# ADC_Buffers.net
KiCad netlist of a schematic drawn in Altium Designer
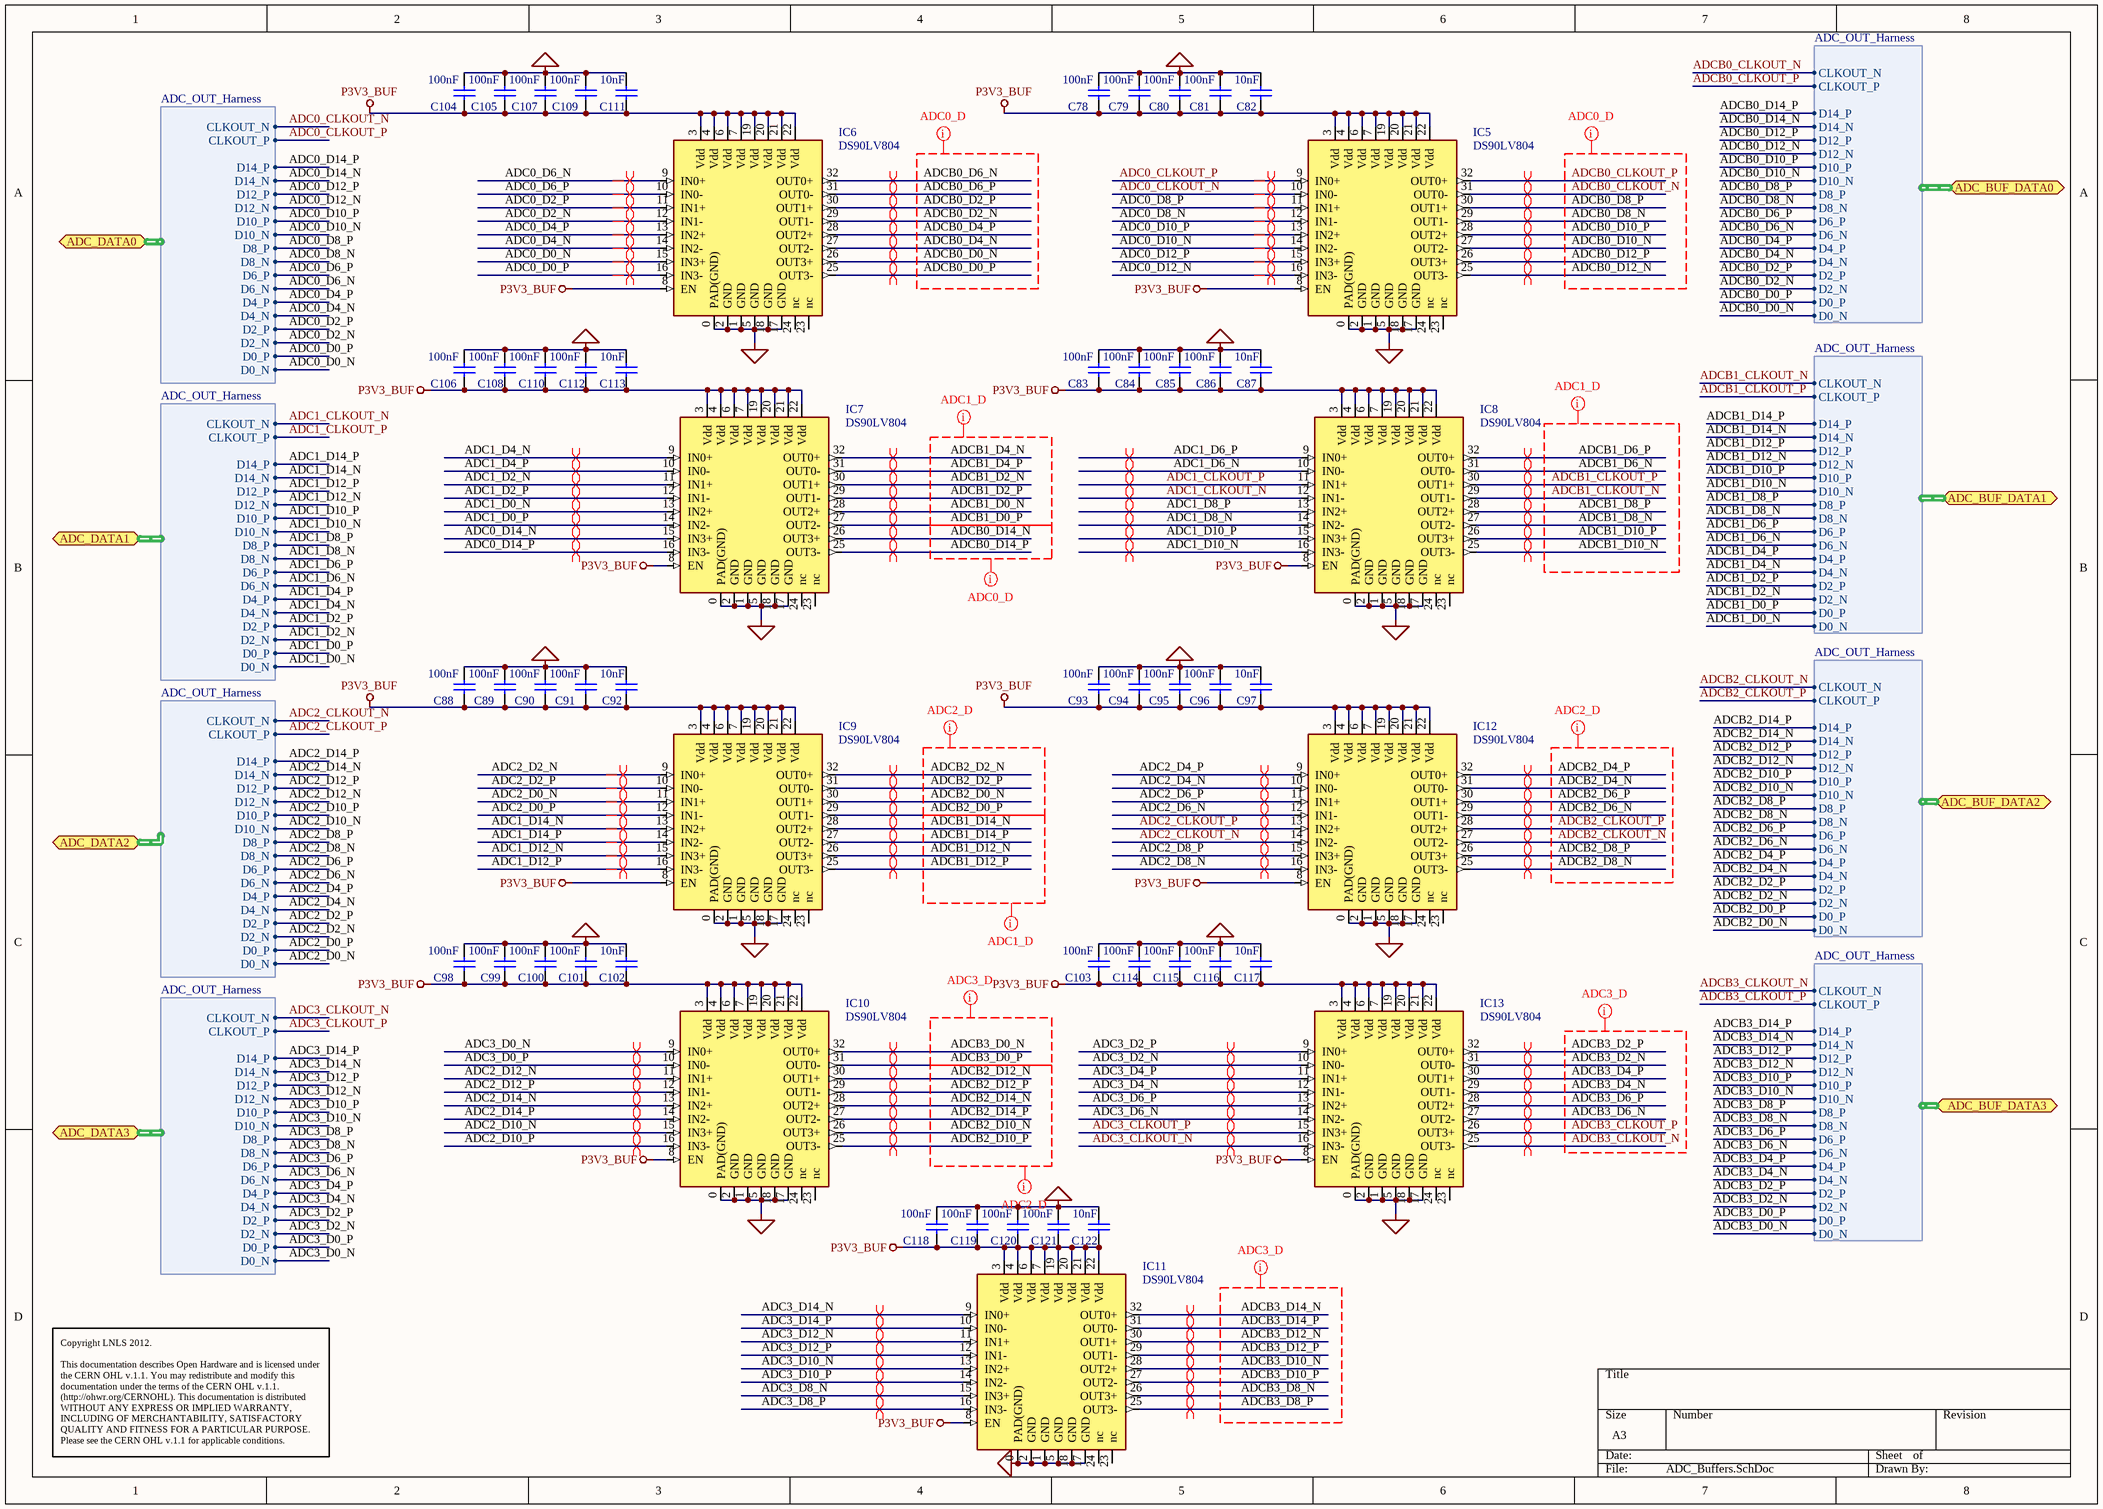
[diagram p0: ADC_Buffers.SchDoc]

(export (version "E")
  (design (tool "Eeschema 10.0.6"))
  (components
    (comp (ref "C78")
      (value "100nF")
      (footprint "CAPC0603X33N")
      (description "Non-polarised capacitor")
      (fields
        (field (name "PART NUMBER") "CC0201_100NF_6.3V_10%_X5R")
        (field (name "VOLTAGE") "6.3V")
        (field (name "AUTHOR") "CERN DEM JLC")
      )
      (libsource (lib "Capacitors") (part "Capacitor - non polarized"))
    )
    (comp (ref "C79")
      (value "100nF")
      (footprint "CAPC0603X33N")
      (description "Non-polarised capacitor")
      (fields
        (field (name "PART NUMBER") "CC0201_100NF_6.3V_10%_X5R")
        (field (name "VOLTAGE") "6.3V")
        (field (name "AUTHOR") "CERN DEM JLC")
      )
      (libsource (lib "Capacitors") (part "Capacitor - non polarized"))
    )
    (comp (ref "C80")
      (value "100nF")
      (footprint "CAPC0603X33N")
      (description "Non-polarised capacitor")
      (fields
        (field (name "PART NUMBER") "CC0201_100NF_6.3V_10%_X5R")
        (field (name "VOLTAGE") "6.3V")
        (field (name "AUTHOR") "CERN DEM JLC")
      )
      (libsource (lib "Capacitors") (part "Capacitor - non polarized"))
    )
    (comp (ref "C81")
      (value "100nF")
      (footprint "CAPC0603X33N")
      (description "Non-polarised capacitor")
      (fields
        (field (name "PART NUMBER") "CC0201_100NF_6.3V_10%_X5R")
        (field (name "VOLTAGE") "6.3V")
        (field (name "AUTHOR") "CERN DEM JLC")
      )
      (libsource (lib "Capacitors") (part "Capacitor - non polarized"))
    )
    (comp (ref "C82")
      (value "10nF")
      (footprint "CAPC0603X33N")
      (description "Non-polarised capacitor")
      (fields
        (field (name "PART NUMBER") "CC0201_10NF_10V_10%_X5R")
        (field (name "VOLTAGE") "10V")
        (field (name "AUTHOR") "CERN DEM JLC")
      )
      (libsource (lib "Capacitors") (part "Capacitor - non polarized"))
    )
    (comp (ref "C83")
      (value "100nF")
      (footprint "CAPC0603X33N")
      (description "Non-polarised capacitor")
      (fields
        (field (name "PART NUMBER") "CC0201_100NF_6.3V_10%_X5R")
        (field (name "VOLTAGE") "6.3V")
        (field (name "AUTHOR") "CERN DEM JLC")
      )
      (libsource (lib "Capacitors") (part "Capacitor - non polarized"))
    )
    (comp (ref "C84")
      (value "100nF")
      (footprint "CAPC0603X33N")
      (description "Non-polarised capacitor")
      (fields
        (field (name "PART NUMBER") "CC0201_100NF_6.3V_10%_X5R")
        (field (name "VOLTAGE") "6.3V")
        (field (name "AUTHOR") "CERN DEM JLC")
      )
      (libsource (lib "Capacitors") (part "Capacitor - non polarized"))
    )
    (comp (ref "C85")
      (value "100nF")
      (footprint "CAPC0603X33N")
      (description "Non-polarised capacitor")
      (fields
        (field (name "PART NUMBER") "CC0201_100NF_6.3V_10%_X5R")
        (field (name "VOLTAGE") "6.3V")
        (field (name "AUTHOR") "CERN DEM JLC")
      )
      (libsource (lib "Capacitors") (part "Capacitor - non polarized"))
    )
    (comp (ref "C86")
      (value "100nF")
      (footprint "CAPC0603X33N")
      (description "Non-polarised capacitor")
      (fields
        (field (name "PART NUMBER") "CC0201_100NF_6.3V_10%_X5R")
        (field (name "VOLTAGE") "6.3V")
        (field (name "AUTHOR") "CERN DEM JLC")
      )
      (libsource (lib "Capacitors") (part "Capacitor - non polarized"))
    )
    (comp (ref "C87")
      (value "10nF")
      (footprint "CAPC0603X33N")
      (description "Non-polarised capacitor")
      (fields
        (field (name "PART NUMBER") "CC0201_10NF_10V_10%_X5R")
        (field (name "VOLTAGE") "10V")
        (field (name "AUTHOR") "CERN DEM JLC")
      )
      (libsource (lib "Capacitors") (part "Capacitor - non polarized"))
    )
    (comp (ref "C88")
      (value "100nF")
      (footprint "CAPC0603X33N")
      (description "Non-polarised capacitor")
      (fields
        (field (name "PART NUMBER") "CC0201_100NF_6.3V_10%_X5R")
        (field (name "VOLTAGE") "6.3V")
        (field (name "AUTHOR") "CERN DEM JLC")
      )
      (libsource (lib "Capacitors") (part "Capacitor - non polarized"))
    )
    (comp (ref "C89")
      (value "100nF")
      (footprint "CAPC0603X33N")
      (description "Non-polarised capacitor")
      (fields
        (field (name "PART NUMBER") "CC0201_100NF_6.3V_10%_X5R")
        (field (name "VOLTAGE") "6.3V")
        (field (name "AUTHOR") "CERN DEM JLC")
      )
      (libsource (lib "Capacitors") (part "Capacitor - non polarized"))
    )
    (comp (ref "C90")
      (value "100nF")
      (footprint "CAPC0603X33N")
      (description "Non-polarised capacitor")
      (fields
        (field (name "PART NUMBER") "CC0201_100NF_6.3V_10%_X5R")
        (field (name "VOLTAGE") "6.3V")
        (field (name "AUTHOR") "CERN DEM JLC")
      )
      (libsource (lib "Capacitors") (part "Capacitor - non polarized"))
    )
    (comp (ref "C91")
      (value "100nF")
      (footprint "CAPC0603X33N")
      (description "Non-polarised capacitor")
      (fields
        (field (name "PART NUMBER") "CC0201_100NF_6.3V_10%_X5R")
        (field (name "VOLTAGE") "6.3V")
        (field (name "AUTHOR") "CERN DEM JLC")
      )
      (libsource (lib "Capacitors") (part "Capacitor - non polarized"))
    )
    (comp (ref "C92")
      (value "10nF")
      (footprint "CAPC0603X33N")
      (description "Non-polarised capacitor")
      (fields
        (field (name "PART NUMBER") "CC0201_10NF_10V_10%_X5R")
        (field (name "VOLTAGE") "10V")
        (field (name "AUTHOR") "CERN DEM JLC")
      )
      (libsource (lib "Capacitors") (part "Capacitor - non polarized"))
    )
    (comp (ref "C93")
      (value "100nF")
      (footprint "CAPC0603X33N")
      (description "Non-polarised capacitor")
      (fields
        (field (name "PART NUMBER") "CC0201_100NF_6.3V_10%_X5R")
        (field (name "VOLTAGE") "6.3V")
        (field (name "AUTHOR") "CERN DEM JLC")
      )
      (libsource (lib "Capacitors") (part "Capacitor - non polarized"))
    )
    (comp (ref "C94")
      (value "100nF")
      (footprint "CAPC0603X33N")
      (description "Non-polarised capacitor")
      (fields
        (field (name "PART NUMBER") "CC0201_100NF_6.3V_10%_X5R")
        (field (name "VOLTAGE") "6.3V")
        (field (name "AUTHOR") "CERN DEM JLC")
      )
      (libsource (lib "Capacitors") (part "Capacitor - non polarized"))
    )
    (comp (ref "C95")
      (value "100nF")
      (footprint "CAPC0603X33N")
      (description "Non-polarised capacitor")
      (fields
        (field (name "PART NUMBER") "CC0201_100NF_6.3V_10%_X5R")
        (field (name "VOLTAGE") "6.3V")
        (field (name "AUTHOR") "CERN DEM JLC")
      )
      (libsource (lib "Capacitors") (part "Capacitor - non polarized"))
    )
    (comp (ref "C96")
      (value "100nF")
      (footprint "CAPC0603X33N")
      (description "Non-polarised capacitor")
      (fields
        (field (name "PART NUMBER") "CC0201_100NF_6.3V_10%_X5R")
        (field (name "VOLTAGE") "6.3V")
        (field (name "AUTHOR") "CERN DEM JLC")
      )
      (libsource (lib "Capacitors") (part "Capacitor - non polarized"))
    )
    (comp (ref "C97")
      (value "10nF")
      (footprint "CAPC0603X33N")
      (description "Non-polarised capacitor")
      (fields
        (field (name "PART NUMBER") "CC0201_10NF_10V_10%_X5R")
        (field (name "VOLTAGE") "10V")
        (field (name "AUTHOR") "CERN DEM JLC")
      )
      (libsource (lib "Capacitors") (part "Capacitor - non polarized"))
    )
    (comp (ref "C98")
      (value "100nF")
      (footprint "CAPC0603X33N")
      (description "Non-polarised capacitor")
      (fields
        (field (name "PART NUMBER") "CC0201_100NF_6.3V_10%_X5R")
        (field (name "VOLTAGE") "6.3V")
        (field (name "AUTHOR") "CERN DEM JLC")
      )
      (libsource (lib "Capacitors") (part "Capacitor - non polarized"))
    )
    (comp (ref "C99")
      (value "100nF")
      (footprint "CAPC0603X33N")
      (description "Non-polarised capacitor")
      (fields
        (field (name "PART NUMBER") "CC0201_100NF_6.3V_10%_X5R")
        (field (name "VOLTAGE") "6.3V")
        (field (name "AUTHOR") "CERN DEM JLC")
      )
      (libsource (lib "Capacitors") (part "Capacitor - non polarized"))
    )
    (comp (ref "C100")
      (value "100nF")
      (footprint "CAPC0603X33N")
      (description "Non-polarised capacitor")
      (fields
        (field (name "PART NUMBER") "CC0201_100NF_6.3V_10%_X5R")
        (field (name "VOLTAGE") "6.3V")
        (field (name "AUTHOR") "CERN DEM JLC")
      )
      (libsource (lib "Capacitors") (part "Capacitor - non polarized"))
    )
    (comp (ref "C101")
      (value "100nF")
      (footprint "CAPC0603X33N")
      (description "Non-polarised capacitor")
      (fields
        (field (name "PART NUMBER") "CC0201_100NF_6.3V_10%_X5R")
        (field (name "VOLTAGE") "6.3V")
        (field (name "AUTHOR") "CERN DEM JLC")
      )
      (libsource (lib "Capacitors") (part "Capacitor - non polarized"))
    )
    (comp (ref "C102")
      (value "10nF")
      (footprint "CAPC0603X33N")
      (description "Non-polarised capacitor")
      (fields
        (field (name "PART NUMBER") "CC0201_10NF_10V_10%_X5R")
        (field (name "VOLTAGE") "10V")
        (field (name "AUTHOR") "CERN DEM JLC")
      )
      (libsource (lib "Capacitors") (part "Capacitor - non polarized"))
    )
    (comp (ref "C103")
      (value "100nF")
      (footprint "CAPC0603X33N")
      (description "Non-polarised capacitor")
      (fields
        (field (name "PART NUMBER") "CC0201_100NF_6.3V_10%_X5R")
        (field (name "VOLTAGE") "6.3V")
        (field (name "AUTHOR") "CERN DEM JLC")
      )
      (libsource (lib "Capacitors") (part "Capacitor - non polarized"))
    )
    (comp (ref "C104")
      (value "100nF")
      (footprint "CAPC0603X33N")
      (description "Non-polarised capacitor")
      (fields
        (field (name "PART NUMBER") "CC0201_100NF_6.3V_10%_X5R")
        (field (name "VOLTAGE") "6.3V")
        (field (name "AUTHOR") "CERN DEM JLC")
      )
      (libsource (lib "Capacitors") (part "Capacitor - non polarized"))
    )
    (comp (ref "C105")
      (value "100nF")
      (footprint "CAPC0603X33N")
      (description "Non-polarised capacitor")
      (fields
        (field (name "PART NUMBER") "CC0201_100NF_6.3V_10%_X5R")
        (field (name "VOLTAGE") "6.3V")
        (field (name "AUTHOR") "CERN DEM JLC")
      )
      (libsource (lib "Capacitors") (part "Capacitor - non polarized"))
    )
    (comp (ref "C106")
      (value "100nF")
      (footprint "CAPC0603X33N")
      (description "Non-polarised capacitor")
      (fields
        (field (name "PART NUMBER") "CC0201_100NF_6.3V_10%_X5R")
        (field (name "VOLTAGE") "6.3V")
        (field (name "AUTHOR") "CERN DEM JLC")
      )
      (libsource (lib "Capacitors") (part "Capacitor - non polarized"))
    )
    (comp (ref "C107")
      (value "100nF")
      (footprint "CAPC0603X33N")
      (description "Non-polarised capacitor")
      (fields
        (field (name "PART NUMBER") "CC0201_100NF_6.3V_10%_X5R")
        (field (name "VOLTAGE") "6.3V")
        (field (name "AUTHOR") "CERN DEM JLC")
      )
      (libsource (lib "Capacitors") (part "Capacitor - non polarized"))
    )
    (comp (ref "C108")
      (value "100nF")
      (footprint "CAPC0603X33N")
      (description "Non-polarised capacitor")
      (fields
        (field (name "PART NUMBER") "CC0201_100NF_6.3V_10%_X5R")
        (field (name "VOLTAGE") "6.3V")
        (field (name "AUTHOR") "CERN DEM JLC")
      )
      (libsource (lib "Capacitors") (part "Capacitor - non polarized"))
    )
    (comp (ref "C109")
      (value "100nF")
      (footprint "CAPC0603X33N")
      (description "Non-polarised capacitor")
      (fields
        (field (name "PART NUMBER") "CC0201_100NF_6.3V_10%_X5R")
        (field (name "VOLTAGE") "6.3V")
        (field (name "AUTHOR") "CERN DEM JLC")
      )
      (libsource (lib "Capacitors") (part "Capacitor - non polarized"))
    )
    (comp (ref "C110")
      (value "100nF")
      (footprint "CAPC0603X33N")
      (description "Non-polarised capacitor")
      (fields
        (field (name "PART NUMBER") "CC0201_100NF_6.3V_10%_X5R")
        (field (name "VOLTAGE") "6.3V")
        (field (name "AUTHOR") "CERN DEM JLC")
      )
      (libsource (lib "Capacitors") (part "Capacitor - non polarized"))
    )
    (comp (ref "C111")
      (value "10nF")
      (footprint "CAPC0603X33N")
      (description "Non-polarised capacitor")
      (fields
        (field (name "PART NUMBER") "CC0201_10NF_10V_10%_X5R")
        (field (name "VOLTAGE") "10V")
        (field (name "AUTHOR") "CERN DEM JLC")
      )
      (libsource (lib "Capacitors") (part "Capacitor - non polarized"))
    )
    (comp (ref "C112")
      (value "100nF")
      (footprint "CAPC0603X33N")
      (description "Non-polarised capacitor")
      (fields
        (field (name "PART NUMBER") "CC0201_100NF_6.3V_10%_X5R")
        (field (name "VOLTAGE") "6.3V")
        (field (name "AUTHOR") "CERN DEM JLC")
      )
      (libsource (lib "Capacitors") (part "Capacitor - non polarized"))
    )
    (comp (ref "C113")
      (value "10nF")
      (footprint "CAPC0603X33N")
      (description "Non-polarised capacitor")
      (fields
        (field (name "PART NUMBER") "CC0201_10NF_10V_10%_X5R")
        (field (name "VOLTAGE") "10V")
        (field (name "AUTHOR") "CERN DEM JLC")
      )
      (libsource (lib "Capacitors") (part "Capacitor - non polarized"))
    )
    (comp (ref "C114")
      (value "100nF")
      (footprint "CAPC0603X33N")
      (description "Non-polarised capacitor")
      (fields
        (field (name "PART NUMBER") "CC0201_100NF_6.3V_10%_X5R")
        (field (name "VOLTAGE") "6.3V")
        (field (name "AUTHOR") "CERN DEM JLC")
      )
      (libsource (lib "Capacitors") (part "Capacitor - non polarized"))
    )
    (comp (ref "C115")
      (value "100nF")
      (footprint "CAPC0603X33N")
      (description "Non-polarised capacitor")
      (fields
        (field (name "PART NUMBER") "CC0201_100NF_6.3V_10%_X5R")
        (field (name "VOLTAGE") "6.3V")
        (field (name "AUTHOR") "CERN DEM JLC")
      )
      (libsource (lib "Capacitors") (part "Capacitor - non polarized"))
    )
    (comp (ref "C116")
      (value "100nF")
      (footprint "CAPC0603X33N")
      (description "Non-polarised capacitor")
      (fields
        (field (name "PART NUMBER") "CC0201_100NF_6.3V_10%_X5R")
        (field (name "VOLTAGE") "6.3V")
        (field (name "AUTHOR") "CERN DEM JLC")
      )
      (libsource (lib "Capacitors") (part "Capacitor - non polarized"))
    )
    (comp (ref "C117")
      (value "10nF")
      (footprint "CAPC0603X33N")
      (description "Non-polarised capacitor")
      (fields
        (field (name "PART NUMBER") "CC0201_10NF_10V_10%_X5R")
        (field (name "VOLTAGE") "10V")
        (field (name "AUTHOR") "CERN DEM JLC")
      )
      (libsource (lib "Capacitors") (part "Capacitor - non polarized"))
    )
    (comp (ref "C118")
      (value "100nF")
      (footprint "CAPC0603X33N")
      (description "Non-polarised capacitor")
      (fields
        (field (name "PART NUMBER") "CC0201_100NF_6.3V_10%_X5R")
        (field (name "VOLTAGE") "6.3V")
        (field (name "AUTHOR") "CERN DEM JLC")
      )
      (libsource (lib "Capacitors") (part "Capacitor - non polarized"))
    )
    (comp (ref "C119")
      (value "100nF")
      (footprint "CAPC0603X33N")
      (description "Non-polarised capacitor")
      (fields
        (field (name "PART NUMBER") "CC0201_100NF_6.3V_10%_X5R")
        (field (name "VOLTAGE") "6.3V")
        (field (name "AUTHOR") "CERN DEM JLC")
      )
      (libsource (lib "Capacitors") (part "Capacitor - non polarized"))
    )
    (comp (ref "C120")
      (value "100nF")
      (footprint "CAPC0603X33N")
      (description "Non-polarised capacitor")
      (fields
        (field (name "PART NUMBER") "CC0201_100NF_6.3V_10%_X5R")
        (field (name "VOLTAGE") "6.3V")
        (field (name "AUTHOR") "CERN DEM JLC")
      )
      (libsource (lib "Capacitors") (part "Capacitor - non polarized"))
    )
    (comp (ref "C121")
      (value "100nF")
      (footprint "CAPC0603X33N")
      (description "Non-polarised capacitor")
      (fields
        (field (name "PART NUMBER") "CC0201_100NF_6.3V_10%_X5R")
        (field (name "VOLTAGE") "6.3V")
        (field (name "AUTHOR") "CERN DEM JLC")
      )
      (libsource (lib "Capacitors") (part "Capacitor - non polarized"))
    )
    (comp (ref "C122")
      (value "10nF")
      (footprint "CAPC0603X33N")
      (description "Non-polarised capacitor")
      (fields
        (field (name "PART NUMBER") "CC0201_10NF_10V_10%_X5R")
        (field (name "VOLTAGE") "10V")
        (field (name "AUTHOR") "CERN DEM JLC")
      )
      (libsource (lib "Capacitors") (part "Capacitor - non polarized"))
    )
    (comp (ref "IC5")
      (value "DS90LV804")
      (footprint "QFN50P500X500X80-33N-S320")
      (description "4-Channel 800 Mbps LVDS Buffer/Repeater")
      (fields
        (field (name "PART NUMBER") "DS90LV804TSQ")
        (field (name "MANUFACTURER") "TEXAS INSTRUMENTS")
        (field (name "AUTHOR") "LNLS DIG GBMB")
      )
      (libsource (lib "ICs And Semiconductors") (part "DS90LV804"))
    )
    (comp (ref "IC6")
      (value "DS90LV804")
      (footprint "QFN50P500X500X80-33N-S320")
      (description "4-Channel 800 Mbps LVDS Buffer/Repeater")
      (fields
        (field (name "PART NUMBER") "DS90LV804TSQ")
        (field (name "MANUFACTURER") "TEXAS INSTRUMENTS")
        (field (name "AUTHOR") "LNLS DIG GBMB")
      )
      (libsource (lib "ICs And Semiconductors") (part "DS90LV804"))
    )
    (comp (ref "IC7")
      (value "DS90LV804")
      (footprint "LFCSP32")
      (description "4-Channel 800 Mbps LVDS Buffer/Repeater")
      (fields
        (field (name "PART NUMBER") "DS90LV804TSQ")
        (field (name "MANUFACTURER") "TEXAS INSTRUMENTS")
        (field (name "AUTHOR") "LNLS DIG GBMB")
      )
      (libsource (lib "ICs And Semiconductors") (part "DS90LV804"))
    )
    (comp (ref "IC8")
      (value "DS90LV804")
      (footprint "LFCSP32")
      (description "4-Channel 800 Mbps LVDS Buffer/Repeater")
      (fields
        (field (name "PART NUMBER") "DS90LV804TSQ")
        (field (name "MANUFACTURER") "TEXAS INSTRUMENTS")
        (field (name "AUTHOR") "LNLS DIG GBMB")
      )
      (libsource (lib "ICs And Semiconductors") (part "DS90LV804"))
    )
    (comp (ref "IC9")
      (value "DS90LV804")
      (footprint "LFCSP32")
      (description "4-Channel 800 Mbps LVDS Buffer/Repeater")
      (fields
        (field (name "PART NUMBER") "DS90LV804TSQ")
        (field (name "MANUFACTURER") "TEXAS INSTRUMENTS")
        (field (name "AUTHOR") "LNLS DIG GBMB")
      )
      (libsource (lib "ICs And Semiconductors") (part "DS90LV804"))
    )
    (comp (ref "IC10")
      (value "DS90LV804")
      (footprint "LFCSP32")
      (description "4-Channel 800 Mbps LVDS Buffer/Repeater")
      (fields
        (field (name "PART NUMBER") "DS90LV804TSQ")
        (field (name "MANUFACTURER") "TEXAS INSTRUMENTS")
        (field (name "AUTHOR") "LNLS DIG GBMB")
      )
      (libsource (lib "ICs And Semiconductors") (part "DS90LV804"))
    )
    (comp (ref "IC11")
      (value "DS90LV804")
      (footprint "LFCSP32")
      (description "4-Channel 800 Mbps LVDS Buffer/Repeater")
      (fields
        (field (name "PART NUMBER") "DS90LV804TSQ")
        (field (name "MANUFACTURER") "TEXAS INSTRUMENTS")
        (field (name "AUTHOR") "LNLS DIG GBMB")
      )
      (libsource (lib "ICs And Semiconductors") (part "DS90LV804"))
    )
    (comp (ref "IC12")
      (value "DS90LV804")
      (footprint "LFCSP32")
      (description "4-Channel 800 Mbps LVDS Buffer/Repeater")
      (fields
        (field (name "PART NUMBER") "DS90LV804TSQ")
        (field (name "MANUFACTURER") "TEXAS INSTRUMENTS")
        (field (name "AUTHOR") "LNLS DIG GBMB")
      )
      (libsource (lib "ICs And Semiconductors") (part "DS90LV804"))
    )
    (comp (ref "IC13")
      (value "DS90LV804")
      (footprint "LFCSP32")
      (description "4-Channel 800 Mbps LVDS Buffer/Repeater")
      (fields
        (field (name "PART NUMBER") "DS90LV804TSQ")
        (field (name "MANUFACTURER") "TEXAS INSTRUMENTS")
        (field (name "AUTHOR") "LNLS DIG GBMB")
      )
      (libsource (lib "ICs And Semiconductors") (part "DS90LV804"))
    )
  )
  (nets
    (net (code "2") (name "/ADC0_CLKOUT_N") (class "Default")
      (node (ref "IC5") (pin "10") (pinfunction "IN0-_10") (pintype "input"))
    )
    (net (code "3") (name "/ADC0_CLKOUT_P") (class "Default")
      (node (ref "IC5") (pin "9") (pinfunction "IN0+_9") (pintype "input"))
    )
    (net (code "4") (name "/ADC0_D0_N") (class "Default")
      (node (ref "IC6") (pin "15") (pinfunction "IN3+_15") (pintype "input"))
    )
    (net (code "5") (name "/ADC0_D0_P") (class "Default")
      (node (ref "IC6") (pin "16") (pinfunction "IN3-_16") (pintype "input"))
    )
    (net (code "6") (name "/ADC0_D2_N") (class "Default")
      (node (ref "IC6") (pin "12") (pinfunction "IN1-_12") (pintype "input"))
    )
    (net (code "7") (name "/ADC0_D2_P") (class "Default")
      (node (ref "IC6") (pin "11") (pinfunction "IN1+_11") (pintype "input"))
    )
    (net (code "8") (name "/ADC0_D4_N") (class "Default")
      (node (ref "IC6") (pin "14") (pinfunction "IN2-_14") (pintype "input"))
    )
    (net (code "9") (name "/ADC0_D4_P") (class "Default")
      (node (ref "IC6") (pin "13") (pinfunction "IN2+_13") (pintype "input"))
    )
    (net (code "10") (name "/ADC0_D6_N") (class "Default")
      (node (ref "IC6") (pin "9") (pinfunction "IN0+_9") (pintype "input"))
    )
    (net (code "11") (name "/ADC0_D6_P") (class "Default")
      (node (ref "IC6") (pin "10") (pinfunction "IN0-_10") (pintype "input"))
    )
    (net (code "12") (name "/ADC0_D8_N") (class "Default")
      (node (ref "IC5") (pin "12") (pinfunction "IN1-_12") (pintype "input"))
    )
    (net (code "13") (name "/ADC0_D8_P") (class "Default")
      (node (ref "IC5") (pin "11") (pinfunction "IN1+_11") (pintype "input"))
    )
    (net (code "14") (name "/ADC0_D10_N") (class "Default")
      (node (ref "IC5") (pin "14") (pinfunction "IN2-_14") (pintype "input"))
    )
    (net (code "15") (name "/ADC0_D10_P") (class "Default")
      (node (ref "IC5") (pin "13") (pinfunction "IN2+_13") (pintype "input"))
    )
    (net (code "16") (name "/ADC0_D12_N") (class "Default")
      (node (ref "IC5") (pin "16") (pinfunction "IN3-_16") (pintype "input"))
    )
    (net (code "17") (name "/ADC0_D12_P") (class "Default")
      (node (ref "IC5") (pin "15") (pinfunction "IN3+_15") (pintype "input"))
    )
    (net (code "18") (name "/ADC0_D14_N") (class "Default")
      (node (ref "IC7") (pin "15") (pinfunction "IN3+_15") (pintype "input"))
    )
    (net (code "19") (name "/ADC0_D14_P") (class "Default")
      (node (ref "IC7") (pin "16") (pinfunction "IN3-_16") (pintype "input"))
    )
    (net (code "20") (name "/ADC1_CLKOUT_N") (class "Default")
      (node (ref "IC8") (pin "12") (pinfunction "IN1-_12") (pintype "input"))
    )
    (net (code "21") (name "/ADC1_CLKOUT_P") (class "Default")
      (node (ref "IC8") (pin "11") (pinfunction "IN1+_11") (pintype "input"))
    )
    (net (code "22") (name "/ADC1_D0_N") (class "Default")
      (node (ref "IC7") (pin "13") (pinfunction "IN2+_13") (pintype "input"))
    )
    (net (code "23") (name "/ADC1_D0_P") (class "Default")
      (node (ref "IC7") (pin "14") (pinfunction "IN2-_14") (pintype "input"))
    )
    (net (code "24") (name "/ADC1_D2_N") (class "Default")
      (node (ref "IC7") (pin "11") (pinfunction "IN1+_11") (pintype "input"))
    )
    (net (code "25") (name "/ADC1_D2_P") (class "Default")
      (node (ref "IC7") (pin "12") (pinfunction "IN1-_12") (pintype "input"))
    )
    (net (code "26") (name "/ADC1_D4_N") (class "Default")
      (node (ref "IC7") (pin "9") (pinfunction "IN0+_9") (pintype "input"))
    )
    (net (code "27") (name "/ADC1_D4_P") (class "Default")
      (node (ref "IC7") (pin "10") (pinfunction "IN0-_10") (pintype "input"))
    )
    (net (code "28") (name "/ADC1_D6_N") (class "Default")
      (node (ref "IC8") (pin "10") (pinfunction "IN0-_10") (pintype "input"))
    )
    (net (code "29") (name "/ADC1_D6_P") (class "Default")
      (node (ref "IC8") (pin "9") (pinfunction "IN0+_9") (pintype "input"))
    )
    (net (code "30") (name "/ADC1_D8_N") (class "Default")
      (node (ref "IC8") (pin "14") (pinfunction "IN2-_14") (pintype "input"))
    )
    (net (code "31") (name "/ADC1_D8_P") (class "Default")
      (node (ref "IC8") (pin "13") (pinfunction "IN2+_13") (pintype "input"))
    )
    (net (code "32") (name "/ADC1_D10_N") (class "Default")
      (node (ref "IC8") (pin "16") (pinfunction "IN3-_16") (pintype "input"))
    )
    (net (code "33") (name "/ADC1_D10_P") (class "Default")
      (node (ref "IC8") (pin "15") (pinfunction "IN3+_15") (pintype "input"))
    )
    (net (code "34") (name "/ADC1_D12_N") (class "Default")
      (node (ref "IC9") (pin "15") (pinfunction "IN3+_15") (pintype "input"))
    )
    (net (code "35") (name "/ADC1_D12_P") (class "Default")
      (node (ref "IC9") (pin "16") (pinfunction "IN3-_16") (pintype "input"))
    )
    (net (code "36") (name "/ADC1_D14_N") (class "Default")
      (node (ref "IC9") (pin "13") (pinfunction "IN2+_13") (pintype "input"))
    )
    (net (code "37") (name "/ADC1_D14_P") (class "Default")
      (node (ref "IC9") (pin "14") (pinfunction "IN2-_14") (pintype "input"))
    )
    (net (code "38") (name "/ADC2_CLKOUT_N") (class "Default")
      (node (ref "IC12") (pin "14") (pinfunction "IN2-_14") (pintype "input"))
    )
    (net (code "39") (name "/ADC2_CLKOUT_P") (class "Default")
      (node (ref "IC12") (pin "13") (pinfunction "IN2+_13") (pintype "input"))
    )
    (net (code "40") (name "/ADC2_D0_N") (class "Default")
      (node (ref "IC9") (pin "11") (pinfunction "IN1+_11") (pintype "input"))
    )
    (net (code "41") (name "/ADC2_D0_P") (class "Default")
      (node (ref "IC9") (pin "12") (pinfunction "IN1-_12") (pintype "input"))
    )
    (net (code "42") (name "/ADC2_D2_N") (class "Default")
      (node (ref "IC9") (pin "9") (pinfunction "IN0+_9") (pintype "input"))
    )
    (net (code "43") (name "/ADC2_D2_P") (class "Default")
      (node (ref "IC9") (pin "10") (pinfunction "IN0-_10") (pintype "input"))
    )
    (net (code "44") (name "/ADC2_D4_N") (class "Default")
      (node (ref "IC12") (pin "10") (pinfunction "IN0-_10") (pintype "input"))
    )
    (net (code "45") (name "/ADC2_D4_P") (class "Default")
      (node (ref "IC12") (pin "9") (pinfunction "IN0+_9") (pintype "input"))
    )
    (net (code "46") (name "/ADC2_D6_N") (class "Default")
      (node (ref "IC12") (pin "12") (pinfunction "IN1-_12") (pintype "input"))
    )
    (net (code "47") (name "/ADC2_D6_P") (class "Default")
      (node (ref "IC12") (pin "11") (pinfunction "IN1+_11") (pintype "input"))
    )
    (net (code "48") (name "/ADC2_D8_N") (class "Default")
      (node (ref "IC12") (pin "16") (pinfunction "IN3-_16") (pintype "input"))
    )
    (net (code "49") (name "/ADC2_D8_P") (class "Default")
      (node (ref "IC12") (pin "15") (pinfunction "IN3+_15") (pintype "input"))
    )
    (net (code "50") (name "/ADC2_D10_N") (class "Default")
      (node (ref "IC10") (pin "15") (pinfunction "IN3+_15") (pintype "input"))
    )
    (net (code "51") (name "/ADC2_D10_P") (class "Default")
      (node (ref "IC10") (pin "16") (pinfunction "IN3-_16") (pintype "input"))
    )
    (net (code "52") (name "/ADC2_D12_N") (class "Default")
      (node (ref "IC10") (pin "11") (pinfunction "IN1+_11") (pintype "input"))
    )
    (net (code "53") (name "/ADC2_D12_P") (class "Default")
      (node (ref "IC10") (pin "12") (pinfunction "IN1-_12") (pintype "input"))
    )
    (net (code "54") (name "/ADC2_D14_N") (class "Default")
      (node (ref "IC10") (pin "13") (pinfunction "IN2+_13") (pintype "input"))
    )
    (net (code "55") (name "/ADC2_D14_P") (class "Default")
      (node (ref "IC10") (pin "14") (pinfunction "IN2-_14") (pintype "input"))
    )
    (net (code "56") (name "/ADC3_CLKOUT_N") (class "Default")
      (node (ref "IC13") (pin "16") (pinfunction "IN3-_16") (pintype "input"))
    )
    (net (code "57") (name "/ADC3_CLKOUT_P") (class "Default")
      (node (ref "IC13") (pin "15") (pinfunction "IN3+_15") (pintype "input"))
    )
    (net (code "58") (name "/ADC3_D0_N") (class "Default")
      (node (ref "IC10") (pin "9") (pinfunction "IN0+_9") (pintype "input"))
    )
    (net (code "59") (name "/ADC3_D0_P") (class "Default")
      (node (ref "IC10") (pin "10") (pinfunction "IN0-_10") (pintype "input"))
    )
    (net (code "60") (name "/ADC3_D2_N") (class "Default")
      (node (ref "IC13") (pin "10") (pinfunction "IN0-_10") (pintype "input"))
    )
    (net (code "61") (name "/ADC3_D2_P") (class "Default")
      (node (ref "IC13") (pin "9") (pinfunction "IN0+_9") (pintype "input"))
    )
    (net (code "62") (name "/ADC3_D4_N") (class "Default")
      (node (ref "IC13") (pin "12") (pinfunction "IN1-_12") (pintype "input"))
    )
    (net (code "63") (name "/ADC3_D4_P") (class "Default")
      (node (ref "IC13") (pin "11") (pinfunction "IN1+_11") (pintype "input"))
    )
    (net (code "64") (name "/ADC3_D6_N") (class "Default")
      (node (ref "IC13") (pin "14") (pinfunction "IN2-_14") (pintype "input"))
    )
    (net (code "65") (name "/ADC3_D6_P") (class "Default")
      (node (ref "IC13") (pin "13") (pinfunction "IN2+_13") (pintype "input"))
    )
    (net (code "66") (name "/ADC3_D8_N") (class "Default")
      (node (ref "IC11") (pin "15") (pinfunction "IN3+_15") (pintype "input"))
    )
    (net (code "67") (name "/ADC3_D8_P") (class "Default")
      (node (ref "IC11") (pin "16") (pinfunction "IN3-_16") (pintype "input"))
    )
    (net (code "68") (name "/ADC3_D10_N") (class "Default")
      (node (ref "IC11") (pin "13") (pinfunction "IN2+_13") (pintype "input"))
    )
    (net (code "69") (name "/ADC3_D10_P") (class "Default")
      (node (ref "IC11") (pin "14") (pinfunction "IN2-_14") (pintype "input"))
    )
    (net (code "70") (name "/ADC3_D12_N") (class "Default")
      (node (ref "IC11") (pin "11") (pinfunction "IN1+_11") (pintype "input"))
    )
    (net (code "71") (name "/ADC3_D12_P") (class "Default")
      (node (ref "IC11") (pin "12") (pinfunction "IN1-_12") (pintype "input"))
    )
    (net (code "72") (name "/ADC3_D14_N") (class "Default")
      (node (ref "IC11") (pin "9") (pinfunction "IN0+_9") (pintype "input"))
    )
    (net (code "73") (name "/ADC3_D14_P") (class "Default")
      (node (ref "IC11") (pin "10") (pinfunction "IN0-_10") (pintype "input"))
    )
    (net (code "74") (name "/ADCB0_CLKOUT_N") (class "Default")
      (node (ref "IC5") (pin "31") (pinfunction "OUT0-_31") (pintype "output"))
    )
    (net (code "75") (name "/ADCB0_CLKOUT_P") (class "Default")
      (node (ref "IC5") (pin "32") (pinfunction "OUT0+_32") (pintype "output"))
    )
    (net (code "76") (name "/ADCB0_D0_N") (class "Default")
      (node (ref "IC6") (pin "26") (pinfunction "OUT3+_26") (pintype "output"))
    )
    (net (code "77") (name "/ADCB0_D0_P") (class "Default")
      (node (ref "IC6") (pin "25") (pinfunction "OUT3-_25") (pintype "output"))
    )
    (net (code "78") (name "/ADCB0_D2_N") (class "Default")
      (node (ref "IC6") (pin "29") (pinfunction "OUT1-_29") (pintype "output"))
    )
    (net (code "79") (name "/ADCB0_D2_P") (class "Default")
      (node (ref "IC6") (pin "30") (pinfunction "OUT1+_30") (pintype "output"))
    )
    (net (code "80") (name "/ADCB0_D4_N") (class "Default")
      (node (ref "IC6") (pin "27") (pinfunction "OUT2-_27") (pintype "output"))
    )
    (net (code "81") (name "/ADCB0_D4_P") (class "Default")
      (node (ref "IC6") (pin "28") (pinfunction "OUT2+_28") (pintype "output"))
    )
    (net (code "82") (name "/ADCB0_D6_N") (class "Default")
      (node (ref "IC6") (pin "32") (pinfunction "OUT0+_32") (pintype "output"))
    )
    (net (code "83") (name "/ADCB0_D6_P") (class "Default")
      (node (ref "IC6") (pin "31") (pinfunction "OUT0-_31") (pintype "output"))
    )
    (net (code "84") (name "/ADCB0_D8_N") (class "Default")
      (node (ref "IC5") (pin "29") (pinfunction "OUT1-_29") (pintype "output"))
    )
    (net (code "85") (name "/ADCB0_D8_P") (class "Default")
      (node (ref "IC5") (pin "30") (pinfunction "OUT1+_30") (pintype "output"))
    )
    (net (code "86") (name "/ADCB0_D10_N") (class "Default")
      (node (ref "IC5") (pin "27") (pinfunction "OUT2-_27") (pintype "output"))
    )
    (net (code "87") (name "/ADCB0_D10_P") (class "Default")
      (node (ref "IC5") (pin "28") (pinfunction "OUT2+_28") (pintype "output"))
    )
    (net (code "88") (name "/ADCB0_D12_N") (class "Default")
      (node (ref "IC5") (pin "25") (pinfunction "OUT3-_25") (pintype "output"))
    )
    (net (code "89") (name "/ADCB0_D12_P") (class "Default")
      (node (ref "IC5") (pin "26") (pinfunction "OUT3+_26") (pintype "output"))
    )
    (net (code "90") (name "/ADCB0_D14_N") (class "Default")
      (node (ref "IC7") (pin "26") (pinfunction "OUT3+_26") (pintype "output"))
    )
    (net (code "91") (name "/ADCB0_D14_P") (class "Default")
      (node (ref "IC7") (pin "25") (pinfunction "OUT3-_25") (pintype "output"))
    )
    (net (code "92") (name "/ADCB1_CLKOUT_N") (class "Default")
      (node (ref "IC8") (pin "29") (pinfunction "OUT1-_29") (pintype "output"))
    )
    (net (code "93") (name "/ADCB1_CLKOUT_P") (class "Default")
      (node (ref "IC8") (pin "30") (pinfunction "OUT1+_30") (pintype "output"))
    )
    (net (code "94") (name "/ADCB1_D0_N") (class "Default")
      (node (ref "IC7") (pin "28") (pinfunction "OUT2+_28") (pintype "output"))
    )
    (net (code "95") (name "/ADCB1_D0_P") (class "Default")
      (node (ref "IC7") (pin "27") (pinfunction "OUT2-_27") (pintype "output"))
    )
    (net (code "96") (name "/ADCB1_D2_N") (class "Default")
      (node (ref "IC7") (pin "30") (pinfunction "OUT1+_30") (pintype "output"))
    )
    (net (code "97") (name "/ADCB1_D2_P") (class "Default")
      (node (ref "IC7") (pin "29") (pinfunction "OUT1-_29") (pintype "output"))
    )
    (net (code "98") (name "/ADCB1_D4_N") (class "Default")
      (node (ref "IC7") (pin "32") (pinfunction "OUT0+_32") (pintype "output"))
    )
    (net (code "99") (name "/ADCB1_D4_P") (class "Default")
      (node (ref "IC7") (pin "31") (pinfunction "OUT0-_31") (pintype "output"))
    )
    (net (code "100") (name "/ADCB1_D6_N") (class "Default")
      (node (ref "IC8") (pin "31") (pinfunction "OUT0-_31") (pintype "output"))
    )
    (net (code "101") (name "/ADCB1_D6_P") (class "Default")
      (node (ref "IC8") (pin "32") (pinfunction "OUT0+_32") (pintype "output"))
    )
    (net (code "102") (name "/ADCB1_D8_N") (class "Default")
      (node (ref "IC8") (pin "27") (pinfunction "OUT2-_27") (pintype "output"))
    )
    (net (code "103") (name "/ADCB1_D8_P") (class "Default")
      (node (ref "IC8") (pin "28") (pinfunction "OUT2+_28") (pintype "output"))
    )
    (net (code "104") (name "/ADCB1_D10_N") (class "Default")
      (node (ref "IC8") (pin "25") (pinfunction "OUT3-_25") (pintype "output"))
    )
    (net (code "105") (name "/ADCB1_D10_P") (class "Default")
      (node (ref "IC8") (pin "26") (pinfunction "OUT3+_26") (pintype "output"))
    )
    (net (code "106") (name "/ADCB1_D12_N") (class "Default")
      (node (ref "IC9") (pin "26") (pinfunction "OUT3+_26") (pintype "output"))
    )
    (net (code "107") (name "/ADCB1_D12_P") (class "Default")
      (node (ref "IC9") (pin "25") (pinfunction "OUT3-_25") (pintype "output"))
    )
    (net (code "108") (name "/ADCB1_D14_N") (class "Default")
      (node (ref "IC9") (pin "28") (pinfunction "OUT2+_28") (pintype "output"))
    )
    (net (code "109") (name "/ADCB1_D14_P") (class "Default")
      (node (ref "IC9") (pin "27") (pinfunction "OUT2-_27") (pintype "output"))
    )
    (net (code "110") (name "/ADCB2_CLKOUT_N") (class "Default")
      (node (ref "IC12") (pin "27") (pinfunction "OUT2-_27") (pintype "output"))
    )
    (net (code "111") (name "/ADCB2_CLKOUT_P") (class "Default")
      (node (ref "IC12") (pin "28") (pinfunction "OUT2+_28") (pintype "output"))
    )
    (net (code "112") (name "/ADCB2_D0_N") (class "Default")
      (node (ref "IC9") (pin "30") (pinfunction "OUT1+_30") (pintype "output"))
    )
    (net (code "113") (name "/ADCB2_D0_P") (class "Default")
      (node (ref "IC9") (pin "29") (pinfunction "OUT1-_29") (pintype "output"))
    )
    (net (code "114") (name "/ADCB2_D2_N") (class "Default")
      (node (ref "IC9") (pin "32") (pinfunction "OUT0+_32") (pintype "output"))
    )
    (net (code "115") (name "/ADCB2_D2_P") (class "Default")
      (node (ref "IC9") (pin "31") (pinfunction "OUT0-_31") (pintype "output"))
    )
    (net (code "116") (name "/ADCB2_D4_N") (class "Default")
      (node (ref "IC12") (pin "31") (pinfunction "OUT0-_31") (pintype "output"))
    )
    (net (code "117") (name "/ADCB2_D4_P") (class "Default")
      (node (ref "IC12") (pin "32") (pinfunction "OUT0+_32") (pintype "output"))
    )
    (net (code "118") (name "/ADCB2_D6_N") (class "Default")
      (node (ref "IC12") (pin "29") (pinfunction "OUT1-_29") (pintype "output"))
    )
    (net (code "119") (name "/ADCB2_D6_P") (class "Default")
      (node (ref "IC12") (pin "30") (pinfunction "OUT1+_30") (pintype "output"))
    )
    (net (code "120") (name "/ADCB2_D8_N") (class "Default")
      (node (ref "IC12") (pin "25") (pinfunction "OUT3-_25") (pintype "output"))
    )
    (net (code "121") (name "/ADCB2_D8_P") (class "Default")
      (node (ref "IC12") (pin "26") (pinfunction "OUT3+_26") (pintype "output"))
    )
    (net (code "122") (name "/ADCB2_D10_N") (class "Default")
      (node (ref "IC10") (pin "26") (pinfunction "OUT3+_26") (pintype "output"))
    )
    (net (code "123") (name "/ADCB2_D10_P") (class "Default")
      (node (ref "IC10") (pin "25") (pinfunction "OUT3-_25") (pintype "output"))
    )
    (net (code "124") (name "/ADCB2_D12_N") (class "Default")
      (node (ref "IC10") (pin "30") (pinfunction "OUT1+_30") (pintype "output"))
    )
    (net (code "125") (name "/ADCB2_D12_P") (class "Default")
      (node (ref "IC10") (pin "29") (pinfunction "OUT1-_29") (pintype "output"))
    )
    (net (code "126") (name "/ADCB2_D14_N") (class "Default")
      (node (ref "IC10") (pin "28") (pinfunction "OUT2+_28") (pintype "output"))
    )
    (net (code "127") (name "/ADCB2_D14_P") (class "Default")
      (node (ref "IC10") (pin "27") (pinfunction "OUT2-_27") (pintype "output"))
    )
    (net (code "128") (name "/ADCB3_CLKOUT_N") (class "Default")
      (node (ref "IC13") (pin "25") (pinfunction "OUT3-_25") (pintype "output"))
    )
    (net (code "129") (name "/ADCB3_CLKOUT_P") (class "Default")
      (node (ref "IC13") (pin "26") (pinfunction "OUT3+_26") (pintype "output"))
    )
    (net (code "130") (name "/ADCB3_D0_N") (class "Default")
      (node (ref "IC10") (pin "32") (pinfunction "OUT0+_32") (pintype "output"))
    )
    (net (code "131") (name "/ADCB3_D0_P") (class "Default")
      (node (ref "IC10") (pin "31") (pinfunction "OUT0-_31") (pintype "output"))
    )
    (net (code "132") (name "/ADCB3_D2_N") (class "Default")
      (node (ref "IC13") (pin "31") (pinfunction "OUT0-_31") (pintype "output"))
    )
    (net (code "133") (name "/ADCB3_D2_P") (class "Default")
      (node (ref "IC13") (pin "32") (pinfunction "OUT0+_32") (pintype "output"))
    )
    (net (code "134") (name "/ADCB3_D4_N") (class "Default")
      (node (ref "IC13") (pin "29") (pinfunction "OUT1-_29") (pintype "output"))
    )
    (net (code "135") (name "/ADCB3_D4_P") (class "Default")
      (node (ref "IC13") (pin "30") (pinfunction "OUT1+_30") (pintype "output"))
    )
    (net (code "136") (name "/ADCB3_D6_N") (class "Default")
      (node (ref "IC13") (pin "27") (pinfunction "OUT2-_27") (pintype "output"))
    )
    (net (code "137") (name "/ADCB3_D6_P") (class "Default")
      (node (ref "IC13") (pin "28") (pinfunction "OUT2+_28") (pintype "output"))
    )
    (net (code "138") (name "/ADCB3_D8_N") (class "Default")
      (node (ref "IC11") (pin "26") (pinfunction "OUT3+_26") (pintype "output"))
    )
    (net (code "139") (name "/ADCB3_D8_P") (class "Default")
      (node (ref "IC11") (pin "25") (pinfunction "OUT3-_25") (pintype "output"))
    )
    (net (code "140") (name "/ADCB3_D10_N") (class "Default")
      (node (ref "IC11") (pin "28") (pinfunction "OUT2+_28") (pintype "output"))
    )
    (net (code "141") (name "/ADCB3_D10_P") (class "Default")
      (node (ref "IC11") (pin "27") (pinfunction "OUT2-_27") (pintype "output"))
    )
    (net (code "142") (name "/ADCB3_D12_N") (class "Default")
      (node (ref "IC11") (pin "30") (pinfunction "OUT1+_30") (pintype "output"))
    )
    (net (code "143") (name "/ADCB3_D12_P") (class "Default")
      (node (ref "IC11") (pin "29") (pinfunction "OUT1-_29") (pintype "output"))
    )
    (net (code "144") (name "/ADCB3_D14_N") (class "Default")
      (node (ref "IC11") (pin "32") (pinfunction "OUT0+_32") (pintype "output"))
    )
    (net (code "145") (name "/ADCB3_D14_P") (class "Default")
      (node (ref "IC11") (pin "31") (pinfunction "OUT0-_31") (pintype "output"))
    )
    (net (code "147") (name "GND") (class "Default")
      (node (ref "C100") (pin "1") (pinfunction "1_1") (pintype "passive"))
      (node (ref "C101") (pin "1") (pinfunction "1_1") (pintype "passive"))
      (node (ref "C102") (pin "1") (pinfunction "1_1") (pintype "passive"))
      (node (ref "C103") (pin "1") (pinfunction "1_1") (pintype "passive"))
      (node (ref "C104") (pin "1") (pinfunction "1_1") (pintype "passive"))
      (node (ref "C105") (pin "1") (pinfunction "1_1") (pintype "passive"))
      (node (ref "C106") (pin "1") (pinfunction "1_1") (pintype "passive"))
      (node (ref "C107") (pin "1") (pinfunction "1_1") (pintype "passive"))
      (node (ref "C108") (pin "1") (pinfunction "1_1") (pintype "passive"))
      (node (ref "C109") (pin "1") (pinfunction "1_1") (pintype "passive"))
      (node (ref "C110") (pin "1") (pinfunction "1_1") (pintype "passive"))
      (node (ref "C111") (pin "1") (pinfunction "1_1") (pintype "passive"))
      (node (ref "C112") (pin "1") (pinfunction "1_1") (pintype "passive"))
      (node (ref "C113") (pin "1") (pinfunction "1_1") (pintype "passive"))
      (node (ref "C114") (pin "1") (pinfunction "1_1") (pintype "passive"))
      (node (ref "C115") (pin "1") (pinfunction "1_1") (pintype "passive"))
      (node (ref "C116") (pin "1") (pinfunction "1_1") (pintype "passive"))
      (node (ref "C117") (pin "1") (pinfunction "1_1") (pintype "passive"))
      (node (ref "C118") (pin "1") (pinfunction "1_1") (pintype "passive"))
      (node (ref "C119") (pin "1") (pinfunction "1_1") (pintype "passive"))
      (node (ref "C120") (pin "1") (pinfunction "1_1") (pintype "passive"))
      (node (ref "C121") (pin "1") (pinfunction "1_1") (pintype "passive"))
      (node (ref "C122") (pin "1") (pinfunction "1_1") (pintype "passive"))
      (node (ref "C78") (pin "1") (pinfunction "1_1") (pintype "passive"))
      (node (ref "C79") (pin "1") (pinfunction "1_1") (pintype "passive"))
      (node (ref "C80") (pin "1") (pinfunction "1_1") (pintype "passive"))
      (node (ref "C81") (pin "1") (pinfunction "1_1") (pintype "passive"))
      (node (ref "C82") (pin "1") (pinfunction "1_1") (pintype "passive"))
      (node (ref "C83") (pin "1") (pinfunction "1_1") (pintype "passive"))
      (node (ref "C84") (pin "1") (pinfunction "1_1") (pintype "passive"))
      (node (ref "C85") (pin "1") (pinfunction "1_1") (pintype "passive"))
      (node (ref "C86") (pin "1") (pinfunction "1_1") (pintype "passive"))
      (node (ref "C87") (pin "1") (pinfunction "1_1") (pintype "passive"))
      (node (ref "C88") (pin "1") (pinfunction "1_1") (pintype "passive"))
      (node (ref "C89") (pin "1") (pinfunction "1_1") (pintype "passive"))
      (node (ref "C90") (pin "1") (pinfunction "1_1") (pintype "passive"))
      (node (ref "C91") (pin "1") (pinfunction "1_1") (pintype "passive"))
      (node (ref "C92") (pin "1") (pinfunction "1_1") (pintype "passive"))
      (node (ref "C93") (pin "1") (pinfunction "1_1") (pintype "passive"))
      (node (ref "C94") (pin "1") (pinfunction "1_1") (pintype "passive"))
      (node (ref "C95") (pin "1") (pinfunction "1_1") (pintype "passive"))
      (node (ref "C96") (pin "1") (pinfunction "1_1") (pintype "passive"))
      (node (ref "C97") (pin "1") (pinfunction "1_1") (pintype "passive"))
      (node (ref "C98") (pin "1") (pinfunction "1_1") (pintype "passive"))
      (node (ref "C99") (pin "1") (pinfunction "1_1") (pintype "passive"))
      (node (ref "IC10") (pin "0") (pinfunction "PAD(GND)_0") (pintype "power_in"))
      (node (ref "IC10") (pin "1") (pinfunction "GND_1") (pintype "power_in"))
      (node (ref "IC10") (pin "17") (pinfunction "GND_17") (pintype "power_in"))
      (node (ref "IC10") (pin "18") (pinfunction "GND_18") (pintype "power_in"))
      (node (ref "IC10") (pin "2") (pinfunction "GND_2") (pintype "power_in"))
      (node (ref "IC10") (pin "5") (pinfunction "GND_5") (pintype "power_in"))
      (node (ref "IC11") (pin "0") (pinfunction "PAD(GND)_0") (pintype "power_in"))
      (node (ref "IC11") (pin "1") (pinfunction "GND_1") (pintype "power_in"))
      (node (ref "IC11") (pin "17") (pinfunction "GND_17") (pintype "power_in"))
      (node (ref "IC11") (pin "18") (pinfunction "GND_18") (pintype "power_in"))
      (node (ref "IC11") (pin "2") (pinfunction "GND_2") (pintype "power_in"))
      (node (ref "IC11") (pin "5") (pinfunction "GND_5") (pintype "power_in"))
      (node (ref "IC12") (pin "0") (pinfunction "PAD(GND)_0") (pintype "power_in"))
      (node (ref "IC12") (pin "1") (pinfunction "GND_1") (pintype "power_in"))
      (node (ref "IC12") (pin "17") (pinfunction "GND_17") (pintype "power_in"))
      (node (ref "IC12") (pin "18") (pinfunction "GND_18") (pintype "power_in"))
      (node (ref "IC12") (pin "2") (pinfunction "GND_2") (pintype "power_in"))
      (node (ref "IC12") (pin "5") (pinfunction "GND_5") (pintype "power_in"))
      (node (ref "IC13") (pin "0") (pinfunction "PAD(GND)_0") (pintype "power_in"))
      (node (ref "IC13") (pin "1") (pinfunction "GND_1") (pintype "power_in"))
      (node (ref "IC13") (pin "17") (pinfunction "GND_17") (pintype "power_in"))
      (node (ref "IC13") (pin "18") (pinfunction "GND_18") (pintype "power_in"))
      (node (ref "IC13") (pin "2") (pinfunction "GND_2") (pintype "power_in"))
      (node (ref "IC13") (pin "5") (pinfunction "GND_5") (pintype "power_in"))
      (node (ref "IC5") (pin "0") (pinfunction "PAD(GND)_0") (pintype "power_in"))
      (node (ref "IC5") (pin "1") (pinfunction "GND_1") (pintype "power_in"))
      (node (ref "IC5") (pin "17") (pinfunction "GND_17") (pintype "power_in"))
      (node (ref "IC5") (pin "18") (pinfunction "GND_18") (pintype "power_in"))
      (node (ref "IC5") (pin "2") (pinfunction "GND_2") (pintype "power_in"))
      (node (ref "IC5") (pin "5") (pinfunction "GND_5") (pintype "power_in"))
      (node (ref "IC6") (pin "0") (pinfunction "PAD(GND)_0") (pintype "power_in"))
      (node (ref "IC6") (pin "1") (pinfunction "GND_1") (pintype "power_in"))
      (node (ref "IC6") (pin "17") (pinfunction "GND_17") (pintype "power_in"))
      (node (ref "IC6") (pin "18") (pinfunction "GND_18") (pintype "power_in"))
      (node (ref "IC6") (pin "2") (pinfunction "GND_2") (pintype "power_in"))
      (node (ref "IC6") (pin "5") (pinfunction "GND_5") (pintype "power_in"))
      (node (ref "IC7") (pin "0") (pinfunction "PAD(GND)_0") (pintype "power_in"))
      (node (ref "IC7") (pin "1") (pinfunction "GND_1") (pintype "power_in"))
      (node (ref "IC7") (pin "17") (pinfunction "GND_17") (pintype "power_in"))
      (node (ref "IC7") (pin "18") (pinfunction "GND_18") (pintype "power_in"))
      (node (ref "IC7") (pin "2") (pinfunction "GND_2") (pintype "power_in"))
      (node (ref "IC7") (pin "5") (pinfunction "GND_5") (pintype "power_in"))
      (node (ref "IC8") (pin "0") (pinfunction "PAD(GND)_0") (pintype "power_in"))
      (node (ref "IC8") (pin "1") (pinfunction "GND_1") (pintype "power_in"))
      (node (ref "IC8") (pin "17") (pinfunction "GND_17") (pintype "power_in"))
      (node (ref "IC8") (pin "18") (pinfunction "GND_18") (pintype "power_in"))
      (node (ref "IC8") (pin "2") (pinfunction "GND_2") (pintype "power_in"))
      (node (ref "IC8") (pin "5") (pinfunction "GND_5") (pintype "power_in"))
      (node (ref "IC9") (pin "0") (pinfunction "PAD(GND)_0") (pintype "power_in"))
      (node (ref "IC9") (pin "1") (pinfunction "GND_1") (pintype "power_in"))
      (node (ref "IC9") (pin "17") (pinfunction "GND_17") (pintype "power_in"))
      (node (ref "IC9") (pin "18") (pinfunction "GND_18") (pintype "power_in"))
      (node (ref "IC9") (pin "2") (pinfunction "GND_2") (pintype "power_in"))
      (node (ref "IC9") (pin "5") (pinfunction "GND_5") (pintype "power_in"))
    )
    (net (code "148") (name "P3V3_BUF") (class "Default")
      (node (ref "C100") (pin "2") (pinfunction "2_2") (pintype "passive"))
      (node (ref "C101") (pin "2") (pinfunction "2_2") (pintype "passive"))
      (node (ref "C102") (pin "2") (pinfunction "2_2") (pintype "passive"))
      (node (ref "C103") (pin "2") (pinfunction "2_2") (pintype "passive"))
      (node (ref "C104") (pin "2") (pinfunction "2_2") (pintype "passive"))
      (node (ref "C105") (pin "2") (pinfunction "2_2") (pintype "passive"))
      (node (ref "C106") (pin "2") (pinfunction "2_2") (pintype "passive"))
      (node (ref "C107") (pin "2") (pinfunction "2_2") (pintype "passive"))
      (node (ref "C108") (pin "2") (pinfunction "2_2") (pintype "passive"))
      (node (ref "C109") (pin "2") (pinfunction "2_2") (pintype "passive"))
      (node (ref "C110") (pin "2") (pinfunction "2_2") (pintype "passive"))
      (node (ref "C111") (pin "2") (pinfunction "2_2") (pintype "passive"))
      (node (ref "C112") (pin "2") (pinfunction "2_2") (pintype "passive"))
      (node (ref "C113") (pin "2") (pinfunction "2_2") (pintype "passive"))
      (node (ref "C114") (pin "2") (pinfunction "2_2") (pintype "passive"))
      (node (ref "C115") (pin "2") (pinfunction "2_2") (pintype "passive"))
      (node (ref "C116") (pin "2") (pinfunction "2_2") (pintype "passive"))
      (node (ref "C117") (pin "2") (pinfunction "2_2") (pintype "passive"))
      (node (ref "C118") (pin "2") (pinfunction "2_2") (pintype "passive"))
      (node (ref "C119") (pin "2") (pinfunction "2_2") (pintype "passive"))
      (node (ref "C120") (pin "2") (pinfunction "2_2") (pintype "passive"))
      (node (ref "C121") (pin "2") (pinfunction "2_2") (pintype "passive"))
      (node (ref "C122") (pin "2") (pinfunction "2_2") (pintype "passive"))
      (node (ref "C78") (pin "2") (pinfunction "2_2") (pintype "passive"))
      (node (ref "C79") (pin "2") (pinfunction "2_2") (pintype "passive"))
      (node (ref "C80") (pin "2") (pinfunction "2_2") (pintype "passive"))
      (node (ref "C81") (pin "2") (pinfunction "2_2") (pintype "passive"))
      (node (ref "C82") (pin "2") (pinfunction "2_2") (pintype "passive"))
      (node (ref "C83") (pin "2") (pinfunction "2_2") (pintype "passive"))
      (node (ref "C84") (pin "2") (pinfunction "2_2") (pintype "passive"))
      (node (ref "C85") (pin "2") (pinfunction "2_2") (pintype "passive"))
      (node (ref "C86") (pin "2") (pinfunction "2_2") (pintype "passive"))
      (node (ref "C87") (pin "2") (pinfunction "2_2") (pintype "passive"))
      (node (ref "C88") (pin "2") (pinfunction "2_2") (pintype "passive"))
      (node (ref "C89") (pin "2") (pinfunction "2_2") (pintype "passive"))
      (node (ref "C90") (pin "2") (pinfunction "2_2") (pintype "passive"))
      (node (ref "C91") (pin "2") (pinfunction "2_2") (pintype "passive"))
      (node (ref "C92") (pin "2") (pinfunction "2_2") (pintype "passive"))
      (node (ref "C93") (pin "2") (pinfunction "2_2") (pintype "passive"))
      (node (ref "C94") (pin "2") (pinfunction "2_2") (pintype "passive"))
      (node (ref "C95") (pin "2") (pinfunction "2_2") (pintype "passive"))
      (node (ref "C96") (pin "2") (pinfunction "2_2") (pintype "passive"))
      (node (ref "C97") (pin "2") (pinfunction "2_2") (pintype "passive"))
      (node (ref "C98") (pin "2") (pinfunction "2_2") (pintype "passive"))
      (node (ref "C99") (pin "2") (pinfunction "2_2") (pintype "passive"))
      (node (ref "IC10") (pin "19") (pinfunction "Vdd_19") (pintype "power_in"))
      (node (ref "IC10") (pin "20") (pinfunction "Vdd_20") (pintype "power_in"))
      (node (ref "IC10") (pin "21") (pinfunction "Vdd_21") (pintype "power_in"))
      (node (ref "IC10") (pin "22") (pinfunction "Vdd_22") (pintype "power_in"))
      (node (ref "IC10") (pin "3") (pinfunction "Vdd_3") (pintype "power_in"))
      (node (ref "IC10") (pin "4") (pinfunction "Vdd_4") (pintype "power_in"))
      (node (ref "IC10") (pin "6") (pinfunction "Vdd_6") (pintype "power_in"))
      (node (ref "IC10") (pin "7") (pinfunction "Vdd_7") (pintype "power_in"))
      (node (ref "IC10") (pin "8") (pinfunction "EN_8") (pintype "input"))
      (node (ref "IC11") (pin "19") (pinfunction "Vdd_19") (pintype "power_in"))
      (node (ref "IC11") (pin "20") (pinfunction "Vdd_20") (pintype "power_in"))
      (node (ref "IC11") (pin "21") (pinfunction "Vdd_21") (pintype "power_in"))
      (node (ref "IC11") (pin "22") (pinfunction "Vdd_22") (pintype "power_in"))
      (node (ref "IC11") (pin "3") (pinfunction "Vdd_3") (pintype "power_in"))
      (node (ref "IC11") (pin "4") (pinfunction "Vdd_4") (pintype "power_in"))
      (node (ref "IC11") (pin "6") (pinfunction "Vdd_6") (pintype "power_in"))
      (node (ref "IC11") (pin "7") (pinfunction "Vdd_7") (pintype "power_in"))
      (node (ref "IC11") (pin "8") (pinfunction "EN_8") (pintype "input"))
      (node (ref "IC12") (pin "19") (pinfunction "Vdd_19") (pintype "power_in"))
      (node (ref "IC12") (pin "20") (pinfunction "Vdd_20") (pintype "power_in"))
      (node (ref "IC12") (pin "21") (pinfunction "Vdd_21") (pintype "power_in"))
      (node (ref "IC12") (pin "22") (pinfunction "Vdd_22") (pintype "power_in"))
      (node (ref "IC12") (pin "3") (pinfunction "Vdd_3") (pintype "power_in"))
      (node (ref "IC12") (pin "4") (pinfunction "Vdd_4") (pintype "power_in"))
      (node (ref "IC12") (pin "6") (pinfunction "Vdd_6") (pintype "power_in"))
      (node (ref "IC12") (pin "7") (pinfunction "Vdd_7") (pintype "power_in"))
      (node (ref "IC12") (pin "8") (pinfunction "EN_8") (pintype "input"))
      (node (ref "IC13") (pin "19") (pinfunction "Vdd_19") (pintype "power_in"))
      (node (ref "IC13") (pin "20") (pinfunction "Vdd_20") (pintype "power_in"))
      (node (ref "IC13") (pin "21") (pinfunction "Vdd_21") (pintype "power_in"))
      (node (ref "IC13") (pin "22") (pinfunction "Vdd_22") (pintype "power_in"))
      (node (ref "IC13") (pin "3") (pinfunction "Vdd_3") (pintype "power_in"))
      (node (ref "IC13") (pin "4") (pinfunction "Vdd_4") (pintype "power_in"))
      (node (ref "IC13") (pin "6") (pinfunction "Vdd_6") (pintype "power_in"))
      (node (ref "IC13") (pin "7") (pinfunction "Vdd_7") (pintype "power_in"))
      (node (ref "IC13") (pin "8") (pinfunction "EN_8") (pintype "input"))
      (node (ref "IC5") (pin "19") (pinfunction "Vdd_19") (pintype "power_in"))
      (node (ref "IC5") (pin "20") (pinfunction "Vdd_20") (pintype "power_in"))
      (node (ref "IC5") (pin "21") (pinfunction "Vdd_21") (pintype "power_in"))
      (node (ref "IC5") (pin "22") (pinfunction "Vdd_22") (pintype "power_in"))
      (node (ref "IC5") (pin "3") (pinfunction "Vdd_3") (pintype "power_in"))
      (node (ref "IC5") (pin "4") (pinfunction "Vdd_4") (pintype "power_in"))
      (node (ref "IC5") (pin "6") (pinfunction "Vdd_6") (pintype "power_in"))
      (node (ref "IC5") (pin "7") (pinfunction "Vdd_7") (pintype "power_in"))
      (node (ref "IC5") (pin "8") (pinfunction "EN_8") (pintype "input"))
      (node (ref "IC6") (pin "19") (pinfunction "Vdd_19") (pintype "power_in"))
      (node (ref "IC6") (pin "20") (pinfunction "Vdd_20") (pintype "power_in"))
      (node (ref "IC6") (pin "21") (pinfunction "Vdd_21") (pintype "power_in"))
      (node (ref "IC6") (pin "22") (pinfunction "Vdd_22") (pintype "power_in"))
      (node (ref "IC6") (pin "3") (pinfunction "Vdd_3") (pintype "power_in"))
      (node (ref "IC6") (pin "4") (pinfunction "Vdd_4") (pintype "power_in"))
      (node (ref "IC6") (pin "6") (pinfunction "Vdd_6") (pintype "power_in"))
      (node (ref "IC6") (pin "7") (pinfunction "Vdd_7") (pintype "power_in"))
      (node (ref "IC6") (pin "8") (pinfunction "EN_8") (pintype "input"))
      (node (ref "IC7") (pin "19") (pinfunction "Vdd_19") (pintype "power_in"))
      (node (ref "IC7") (pin "20") (pinfunction "Vdd_20") (pintype "power_in"))
      (node (ref "IC7") (pin "21") (pinfunction "Vdd_21") (pintype "power_in"))
      (node (ref "IC7") (pin "22") (pinfunction "Vdd_22") (pintype "power_in"))
      (node (ref "IC7") (pin "3") (pinfunction "Vdd_3") (pintype "power_in"))
      (node (ref "IC7") (pin "4") (pinfunction "Vdd_4") (pintype "power_in"))
      (node (ref "IC7") (pin "6") (pinfunction "Vdd_6") (pintype "power_in"))
      (node (ref "IC7") (pin "7") (pinfunction "Vdd_7") (pintype "power_in"))
      (node (ref "IC7") (pin "8") (pinfunction "EN_8") (pintype "input"))
      (node (ref "IC8") (pin "19") (pinfunction "Vdd_19") (pintype "power_in"))
      (node (ref "IC8") (pin "20") (pinfunction "Vdd_20") (pintype "power_in"))
      (node (ref "IC8") (pin "21") (pinfunction "Vdd_21") (pintype "power_in"))
      (node (ref "IC8") (pin "22") (pinfunction "Vdd_22") (pintype "power_in"))
      (node (ref "IC8") (pin "3") (pinfunction "Vdd_3") (pintype "power_in"))
      (node (ref "IC8") (pin "4") (pinfunction "Vdd_4") (pintype "power_in"))
      (node (ref "IC8") (pin "6") (pinfunction "Vdd_6") (pintype "power_in"))
      (node (ref "IC8") (pin "7") (pinfunction "Vdd_7") (pintype "power_in"))
      (node (ref "IC8") (pin "8") (pinfunction "EN_8") (pintype "input"))
      (node (ref "IC9") (pin "19") (pinfunction "Vdd_19") (pintype "power_in"))
      (node (ref "IC9") (pin "20") (pinfunction "Vdd_20") (pintype "power_in"))
      (node (ref "IC9") (pin "21") (pinfunction "Vdd_21") (pintype "power_in"))
      (node (ref "IC9") (pin "22") (pinfunction "Vdd_22") (pintype "power_in"))
      (node (ref "IC9") (pin "3") (pinfunction "Vdd_3") (pintype "power_in"))
      (node (ref "IC9") (pin "4") (pinfunction "Vdd_4") (pintype "power_in"))
      (node (ref "IC9") (pin "6") (pinfunction "Vdd_6") (pintype "power_in"))
      (node (ref "IC9") (pin "7") (pinfunction "Vdd_7") (pintype "power_in"))
      (node (ref "IC9") (pin "8") (pinfunction "EN_8") (pintype "input"))
    )
    (net (code "149") (name "unconnected-(IC5-nc-Pad23)") (class "Default")
      (node (ref "IC5") (pin "23") (pinfunction "nc_23") (pintype "passive"))
    )
    (net (code "150") (name "unconnected-(IC5-nc-Pad24)") (class "Default")
      (node (ref "IC5") (pin "24") (pinfunction "nc_24") (pintype "passive"))
    )
    (net (code "151") (name "unconnected-(IC6-nc-Pad23)") (class "Default")
      (node (ref "IC6") (pin "23") (pinfunction "nc_23") (pintype "passive"))
    )
    (net (code "152") (name "unconnected-(IC6-nc-Pad24)") (class "Default")
      (node (ref "IC6") (pin "24") (pinfunction "nc_24") (pintype "passive"))
    )
    (net (code "153") (name "unconnected-(IC7-nc-Pad23)") (class "Default")
      (node (ref "IC7") (pin "23") (pinfunction "nc_23") (pintype "passive"))
    )
    (net (code "154") (name "unconnected-(IC7-nc-Pad24)") (class "Default")
      (node (ref "IC7") (pin "24") (pinfunction "nc_24") (pintype "passive"))
    )
    (net (code "155") (name "unconnected-(IC8-nc-Pad23)") (class "Default")
      (node (ref "IC8") (pin "23") (pinfunction "nc_23") (pintype "passive"))
    )
    (net (code "156") (name "unconnected-(IC8-nc-Pad24)") (class "Default")
      (node (ref "IC8") (pin "24") (pinfunction "nc_24") (pintype "passive"))
    )
    (net (code "157") (name "unconnected-(IC9-nc-Pad23)") (class "Default")
      (node (ref "IC9") (pin "23") (pinfunction "nc_23") (pintype "passive"))
    )
    (net (code "158") (name "unconnected-(IC9-nc-Pad24)") (class "Default")
      (node (ref "IC9") (pin "24") (pinfunction "nc_24") (pintype "passive"))
    )
    (net (code "159") (name "unconnected-(IC10-nc-Pad23)") (class "Default")
      (node (ref "IC10") (pin "23") (pinfunction "nc_23") (pintype "passive"))
    )
    (net (code "160") (name "unconnected-(IC10-nc-Pad24)") (class "Default")
      (node (ref "IC10") (pin "24") (pinfunction "nc_24") (pintype "passive"))
    )
    (net (code "161") (name "unconnected-(IC11-nc-Pad23)") (class "Default")
      (node (ref "IC11") (pin "23") (pinfunction "nc_23") (pintype "passive"))
    )
    (net (code "162") (name "unconnected-(IC11-nc-Pad24)") (class "Default")
      (node (ref "IC11") (pin "24") (pinfunction "nc_24") (pintype "passive"))
    )
    (net (code "163") (name "unconnected-(IC12-nc-Pad23)") (class "Default")
      (node (ref "IC12") (pin "23") (pinfunction "nc_23") (pintype "passive"))
    )
    (net (code "164") (name "unconnected-(IC12-nc-Pad24)") (class "Default")
      (node (ref "IC12") (pin "24") (pinfunction "nc_24") (pintype "passive"))
    )
    (net (code "165") (name "unconnected-(IC13-nc-Pad23)") (class "Default")
      (node (ref "IC13") (pin "23") (pinfunction "nc_23") (pintype "passive"))
    )
    (net (code "166") (name "unconnected-(IC13-nc-Pad24)") (class "Default")
      (node (ref "IC13") (pin "24") (pinfunction "nc_24") (pintype "passive"))
    )
  )
)
